# max6675.net
KiCad netlist of a schematic drawn in EAGLE
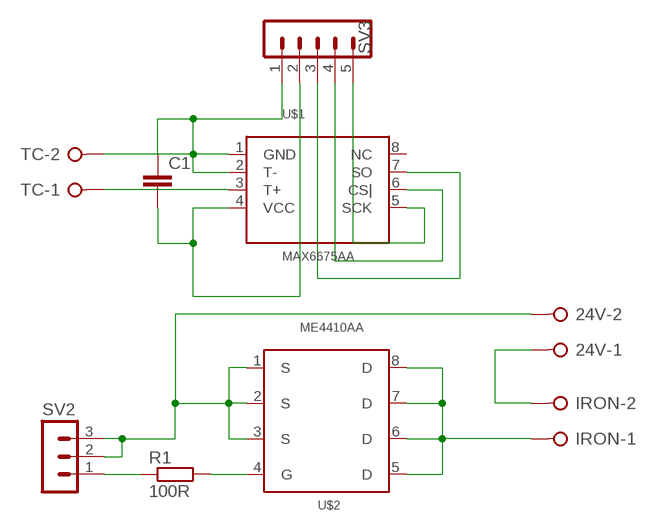
[diagram p0: schematic, sheet 1]

(export (version "E")
  (design (tool "Eeschema 10.0.6"))
  (components
    (comp (ref "24V")
      (value "W237-02P")
      (footprint "eagle-import:W237-132")
      (libsource (lib "eagle-import") (part "W237-02P"))
    )
    (comp (ref "C1")
      (value "C-EU050-025X075")
      (footprint "eagle-import:C050-025X075")
      (libsource (lib "eagle-import") (part "C-EU050-025X075"))
    )
    (comp (ref "IRON")
      (value "W237-02P")
      (footprint "eagle-import:W237-132")
      (libsource (lib "eagle-import") (part "W237-02P"))
    )
    (comp (ref "R1")
      (value "100R")
      (footprint "eagle-import:M1206")
      (libsource (lib "eagle-import") (part "R-EU_M1206"))
    )
    (comp (ref "SV2")
      (value "MA03-1")
      (footprint "eagle-import:MA03-1")
      (libsource (lib "eagle-import") (part "MA03-1"))
    )
    (comp (ref "SV3")
      (value "MA05-1")
      (footprint "eagle-import:MA05-1")
      (libsource (lib "eagle-import") (part "MA05-1"))
    )
    (comp (ref "TC")
      (value "W237-02P")
      (footprint "eagle-import:W237-132")
      (libsource (lib "eagle-import") (part "W237-02P"))
    )
    (comp (ref "U$1")
      (value "MAX6675AA")
      (footprint "eagle-import:SO08")
      (libsource (lib "eagle-import") (part "MAX6675AA"))
    )
    (comp (ref "U$2")
      (value "ME4410AA")
      (footprint "eagle-import:SO-8")
      (libsource (lib "eagle-import") (part "ME4410AA"))
    )
  )
  (nets
    (net (code "1") (name "Net-(24VA-KL)") (class "Default")
      (node (ref "24V") (pin "1") (pinfunction "KL_1") (pintype "passive"))
      (node (ref "IRON") (pin "2") (pinfunction "KL_2") (pintype "passive"))
    )
    (net (code "2") (name "Net-(24VB-KL)") (class "Default")
      (node (ref "24V") (pin "2") (pinfunction "KL_2") (pintype "passive"))
      (node (ref "SV2") (pin "2") (pinfunction "2_2") (pintype "passive"))
      (node (ref "SV2") (pin "3") (pinfunction "3_3") (pintype "passive"))
      (node (ref "U$2") (pin "1") (pinfunction "S_1") (pintype "bidirectional"))
      (node (ref "U$2") (pin "2") (pinfunction "S_2") (pintype "bidirectional"))
      (node (ref "U$2") (pin "3") (pinfunction "S_3") (pintype "bidirectional"))
    )
    (net (code "3") (name "Net-(IRONA-KL)") (class "Default")
      (node (ref "IRON") (pin "1") (pinfunction "KL_1") (pintype "passive"))
      (node (ref "U$2") (pin "5") (pinfunction "D_5") (pintype "bidirectional"))
      (node (ref "U$2") (pin "6") (pinfunction "D_6") (pintype "bidirectional"))
      (node (ref "U$2") (pin "7") (pinfunction "D_7") (pintype "bidirectional"))
      (node (ref "U$2") (pin "8") (pinfunction "D_8") (pintype "bidirectional"))
    )
    (net (code "4") (name "Net-(R1-Pad1)") (class "Default")
      (node (ref "R1") (pin "1") (pinfunction "1_1") (pintype "passive"))
      (node (ref "SV2") (pin "1") (pinfunction "1_1") (pintype "passive"))
    )
    (net (code "5") (name "Net-(TCA-KL)") (class "Default")
      (node (ref "TC") (pin "1") (pinfunction "KL_1") (pintype "passive"))
      (node (ref "U$1") (pin "3") (pinfunction "T+_3") (pintype "bidirectional"))
    )
    (net (code "6") (name "Net-(TCB-KL)") (class "Default")
      (node (ref "C1") (pin "1") (pinfunction "1_1") (pintype "passive"))
      (node (ref "SV3") (pin "1") (pinfunction "1_1") (pintype "passive"))
      (node (ref "TC") (pin "2") (pinfunction "KL_2") (pintype "passive"))
      (node (ref "U$1") (pin "1") (pinfunction "GND_1") (pintype "bidirectional"))
      (node (ref "U$1") (pin "2") (pinfunction "T-_2") (pintype "bidirectional"))
    )
    (net (code "7") (name "Net-(U$1-CS|)") (class "Default")
      (node (ref "SV3") (pin "4") (pinfunction "4_4") (pintype "passive"))
      (node (ref "U$1") (pin "6") (pinfunction "CS|_6") (pintype "bidirectional"))
    )
    (net (code "8") (name "Net-(U$1-SCK)") (class "Default")
      (node (ref "SV3") (pin "5") (pinfunction "5_5") (pintype "passive"))
      (node (ref "U$1") (pin "5") (pinfunction "SCK_5") (pintype "bidirectional"))
    )
    (net (code "9") (name "Net-(U$1-SO)") (class "Default")
      (node (ref "SV3") (pin "3") (pinfunction "3_3") (pintype "passive"))
      (node (ref "U$1") (pin "7") (pinfunction "SO_7") (pintype "bidirectional"))
    )
    (net (code "10") (name "Net-(U$1-VCC)") (class "Default")
      (node (ref "C1") (pin "2") (pinfunction "2_2") (pintype "passive"))
      (node (ref "SV3") (pin "2") (pinfunction "2_2") (pintype "passive"))
      (node (ref "U$1") (pin "4") (pinfunction "VCC_4") (pintype "bidirectional"))
    )
    (net (code "11") (name "Net-(U$2-G)") (class "Default")
      (node (ref "R1") (pin "2") (pinfunction "2_2") (pintype "passive"))
      (node (ref "U$2") (pin "4") (pinfunction "G_4") (pintype "bidirectional"))
    )
    (net (code "12") (name "unconnected-(U$1-NC-Pad8)") (class "Default")
      (node (ref "U$1") (pin "8") (pinfunction "NC_8") (pintype "bidirectional"))
    )
  )
)
